# SCH_Protoboard-2x5x17-2_54-FR4_2026-02-2.net
KiCad netlist of a schematic drawn in EasyEDA
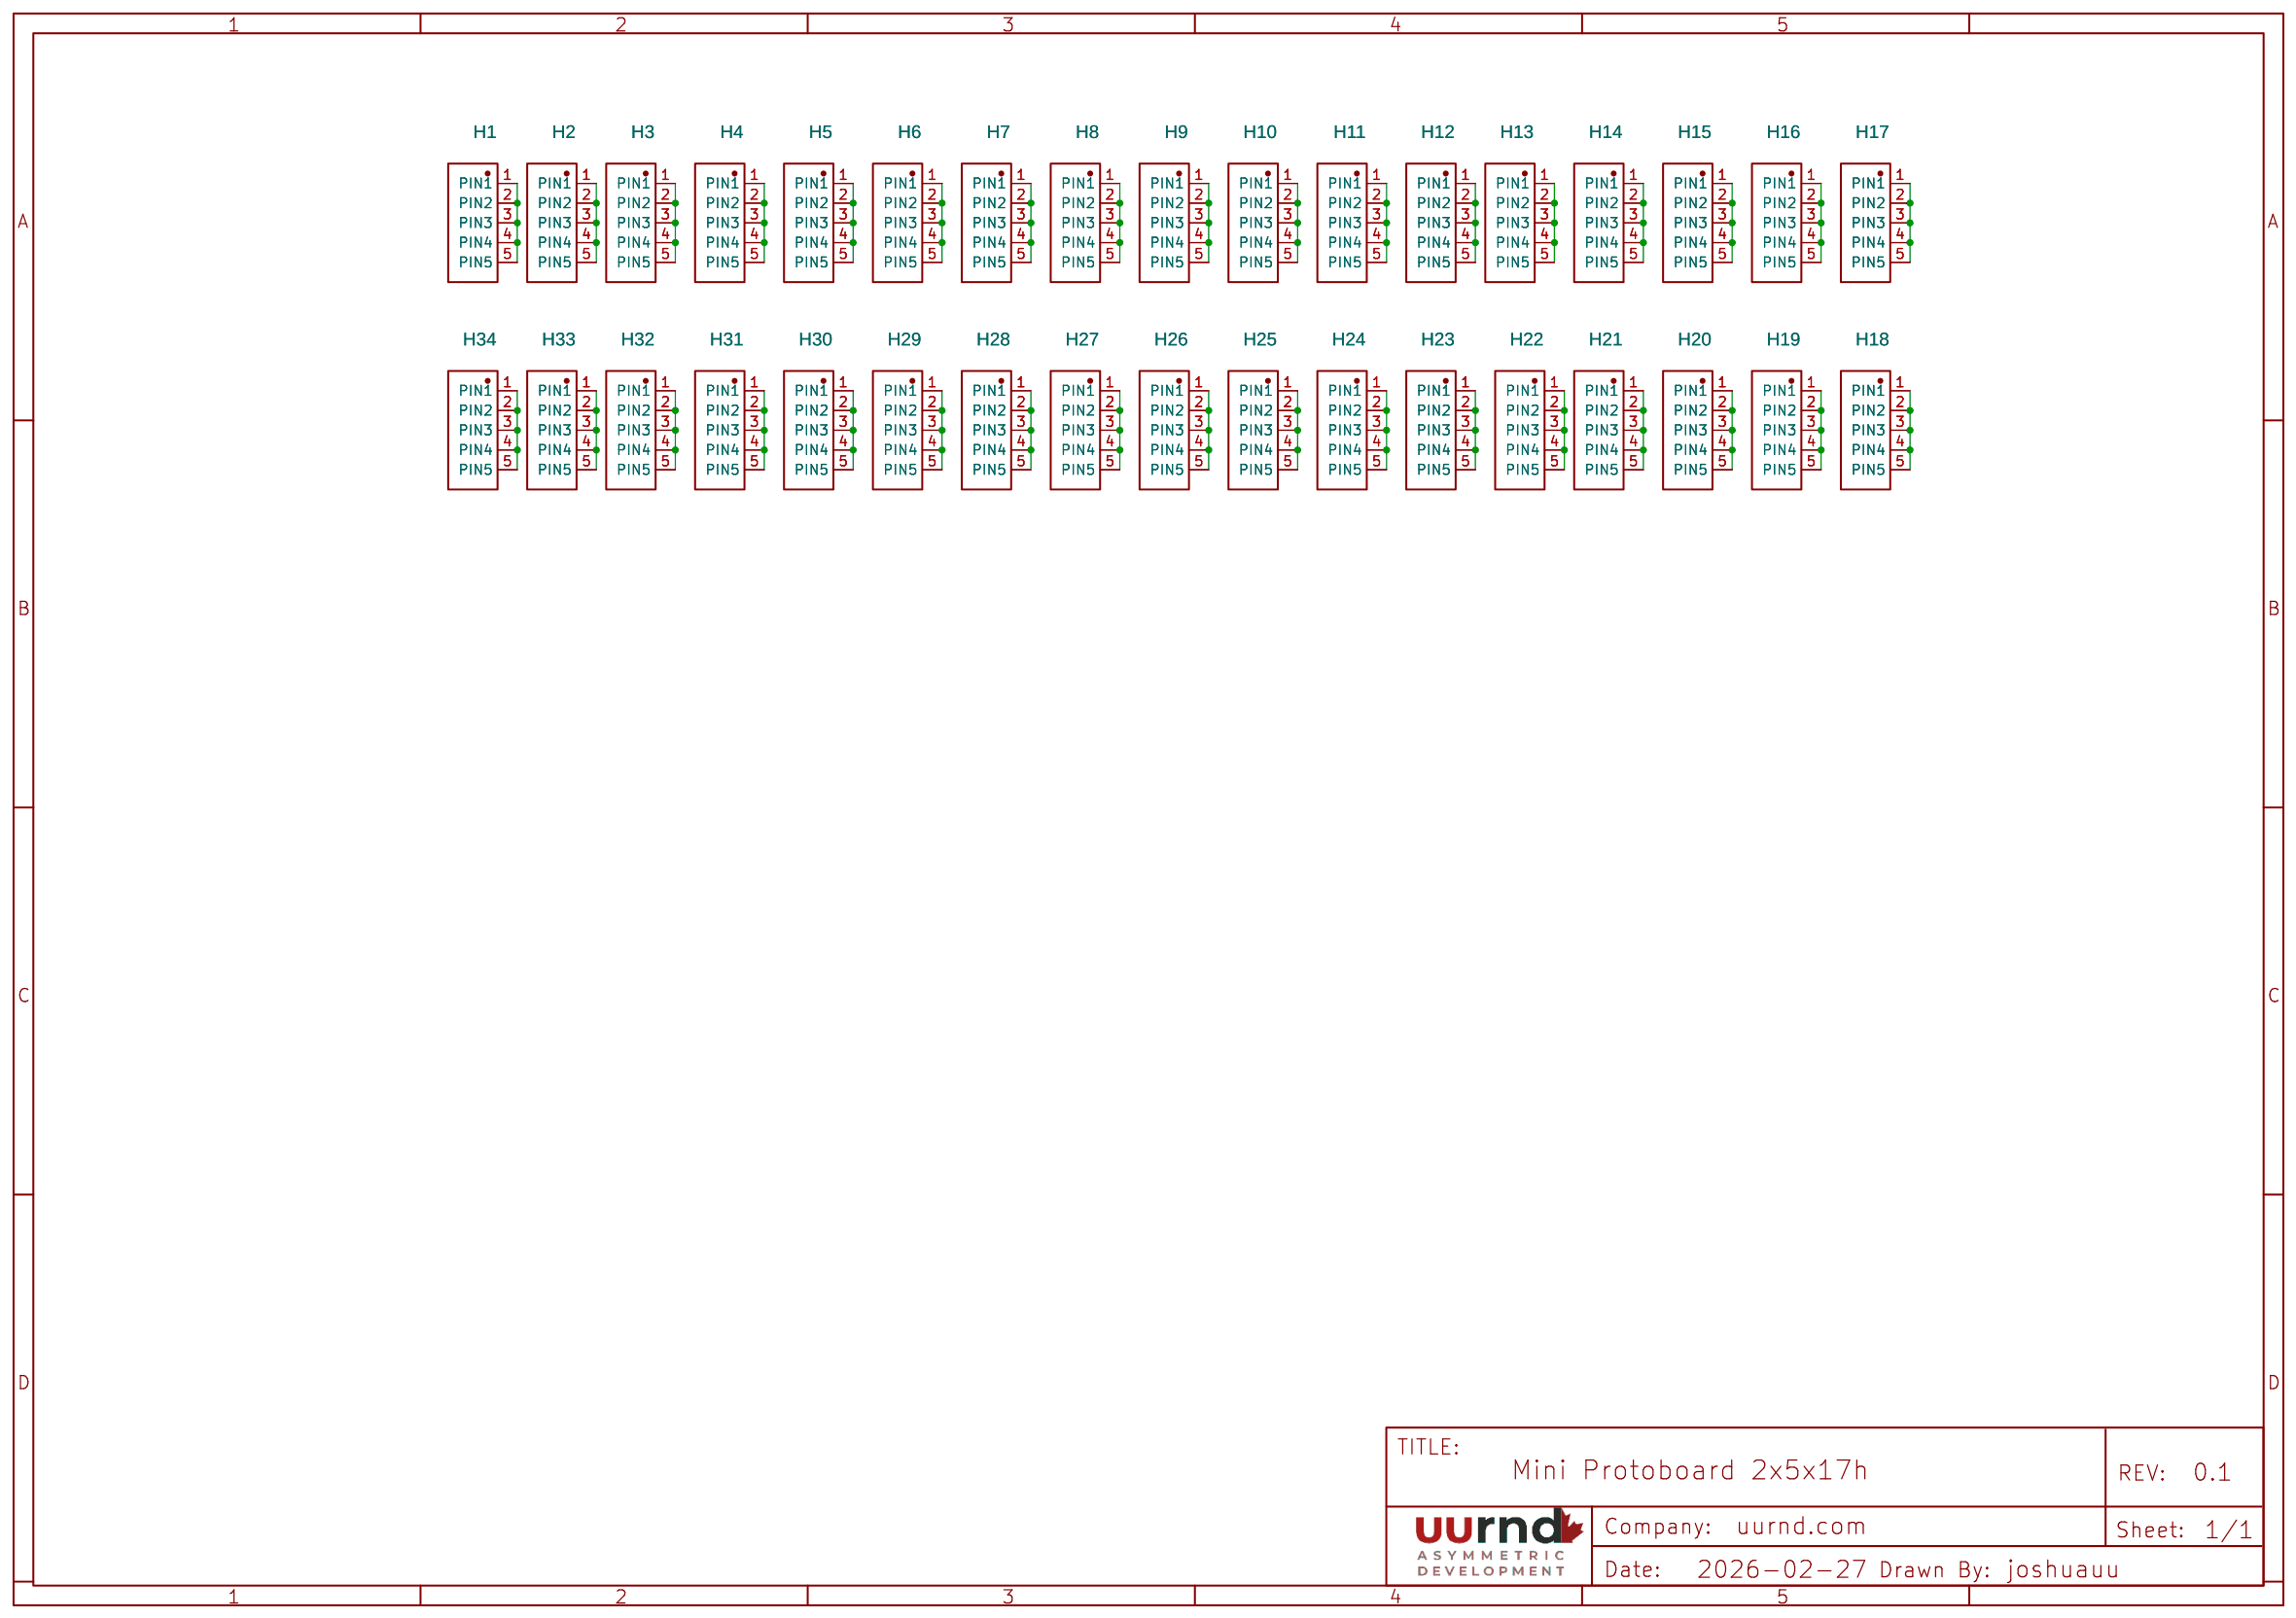
[diagram p0: schematic sheet]

(export (version "E")
  (design (tool "Eeschema 10.0.6"))
  (components
    (comp (ref "H1")
      (value "UU TOP SINGLE SIDE HEADER_2.54MM_1X5P")
      (fields (field (name "Manufacturer") "uuinc"))
      (libsource (lib "") (part "UU TOP SINGLE SIDE HEADER_2.54MM_1X5P"))
    )
    (comp (ref "H2")
      (value "UU TOP SINGLE SIDE HEADER_2.54MM_1X5P")
      (fields (field (name "Manufacturer") "uuinc"))
      (libsource (lib "") (part "UU TOP SINGLE SIDE HEADER_2.54MM_1X5P"))
    )
    (comp (ref "H3")
      (value "UU TOP SINGLE SIDE HEADER_2.54MM_1X5P")
      (fields (field (name "Manufacturer") "uuinc"))
      (libsource (lib "") (part "UU TOP SINGLE SIDE HEADER_2.54MM_1X5P"))
    )
    (comp (ref "H4")
      (value "UU TOP SINGLE SIDE HEADER_2.54MM_1X5P")
      (fields (field (name "Manufacturer") "uuinc"))
      (libsource (lib "") (part "UU TOP SINGLE SIDE HEADER_2.54MM_1X5P"))
    )
    (comp (ref "H5")
      (value "UU TOP SINGLE SIDE HEADER_2.54MM_1X5P")
      (fields (field (name "Manufacturer") "uuinc"))
      (libsource (lib "") (part "UU TOP SINGLE SIDE HEADER_2.54MM_1X5P"))
    )
    (comp (ref "H6")
      (value "UU TOP SINGLE SIDE HEADER_2.54MM_1X5P")
      (fields (field (name "Manufacturer") "uuinc"))
      (libsource (lib "") (part "UU TOP SINGLE SIDE HEADER_2.54MM_1X5P"))
    )
    (comp (ref "H7")
      (value "UU TOP SINGLE SIDE HEADER_2.54MM_1X5P")
      (fields (field (name "Manufacturer") "uuinc"))
      (libsource (lib "") (part "UU TOP SINGLE SIDE HEADER_2.54MM_1X5P"))
    )
    (comp (ref "H8")
      (value "UU TOP SINGLE SIDE HEADER_2.54MM_1X5P")
      (fields (field (name "Manufacturer") "uuinc"))
      (libsource (lib "") (part "UU TOP SINGLE SIDE HEADER_2.54MM_1X5P"))
    )
    (comp (ref "H9")
      (value "UU TOP SINGLE SIDE HEADER_2.54MM_1X5P")
      (fields (field (name "Manufacturer") "uuinc"))
      (libsource (lib "") (part "UU TOP SINGLE SIDE HEADER_2.54MM_1X5P"))
    )
    (comp (ref "H10")
      (value "UU TOP SINGLE SIDE HEADER_2.54MM_1X5P")
      (fields (field (name "Manufacturer") "uuinc"))
      (libsource (lib "") (part "UU TOP SINGLE SIDE HEADER_2.54MM_1X5P"))
    )
    (comp (ref "H11")
      (value "UU TOP SINGLE SIDE HEADER_2.54MM_1X5P")
      (fields (field (name "Manufacturer") "uuinc"))
      (libsource (lib "") (part "UU TOP SINGLE SIDE HEADER_2.54MM_1X5P"))
    )
    (comp (ref "H12")
      (value "UU TOP SINGLE SIDE HEADER_2.54MM_1X5P")
      (fields (field (name "Manufacturer") "uuinc"))
      (libsource (lib "") (part "UU TOP SINGLE SIDE HEADER_2.54MM_1X5P"))
    )
    (comp (ref "H13")
      (value "UU TOP SINGLE SIDE HEADER_2.54MM_1X5P")
      (fields (field (name "Manufacturer") "uuinc"))
      (libsource (lib "") (part "UU TOP SINGLE SIDE HEADER_2.54MM_1X5P"))
    )
    (comp (ref "H14")
      (value "UU TOP SINGLE SIDE HEADER_2.54MM_1X5P")
      (fields (field (name "Manufacturer") "uuinc"))
      (libsource (lib "") (part "UU TOP SINGLE SIDE HEADER_2.54MM_1X5P"))
    )
    (comp (ref "H15")
      (value "UU TOP SINGLE SIDE HEADER_2.54MM_1X5P")
      (fields (field (name "Manufacturer") "uuinc"))
      (libsource (lib "") (part "UU TOP SINGLE SIDE HEADER_2.54MM_1X5P"))
    )
    (comp (ref "H16")
      (value "UU TOP SINGLE SIDE HEADER_2.54MM_1X5P")
      (fields (field (name "Manufacturer") "uuinc"))
      (libsource (lib "") (part "UU TOP SINGLE SIDE HEADER_2.54MM_1X5P"))
    )
    (comp (ref "H17")
      (value "UU TOP SINGLE SIDE HEADER_2.54MM_1X5P")
      (fields (field (name "Manufacturer") "uuinc"))
      (libsource (lib "") (part "UU TOP SINGLE SIDE HEADER_2.54MM_1X5P"))
    )
    (comp (ref "H18")
      (value "UU TOP SINGLE SIDE HEADER_2.54MM_1X5P")
      (fields (field (name "Manufacturer") "uuinc"))
      (libsource (lib "") (part "UU TOP SINGLE SIDE HEADER_2.54MM_1X5P"))
    )
    (comp (ref "H19")
      (value "UU TOP SINGLE SIDE HEADER_2.54MM_1X5P")
      (fields (field (name "Manufacturer") "uuinc"))
      (libsource (lib "") (part "UU TOP SINGLE SIDE HEADER_2.54MM_1X5P"))
    )
    (comp (ref "H20")
      (value "UU TOP SINGLE SIDE HEADER_2.54MM_1X5P")
      (fields (field (name "Manufacturer") "uuinc"))
      (libsource (lib "") (part "UU TOP SINGLE SIDE HEADER_2.54MM_1X5P"))
    )
    (comp (ref "H21")
      (value "UU TOP SINGLE SIDE HEADER_2.54MM_1X5P")
      (fields (field (name "Manufacturer") "uuinc"))
      (libsource (lib "") (part "UU TOP SINGLE SIDE HEADER_2.54MM_1X5P"))
    )
    (comp (ref "H22")
      (value "UU TOP SINGLE SIDE HEADER_2.54MM_1X5P")
      (fields (field (name "Manufacturer") "uuinc"))
      (libsource (lib "") (part "UU TOP SINGLE SIDE HEADER_2.54MM_1X5P"))
    )
    (comp (ref "H23")
      (value "UU TOP SINGLE SIDE HEADER_2.54MM_1X5P")
      (fields (field (name "Manufacturer") "uuinc"))
      (libsource (lib "") (part "UU TOP SINGLE SIDE HEADER_2.54MM_1X5P"))
    )
    (comp (ref "H24")
      (value "UU TOP SINGLE SIDE HEADER_2.54MM_1X5P")
      (fields (field (name "Manufacturer") "uuinc"))
      (libsource (lib "") (part "UU TOP SINGLE SIDE HEADER_2.54MM_1X5P"))
    )
    (comp (ref "H25")
      (value "UU TOP SINGLE SIDE HEADER_2.54MM_1X5P")
      (fields (field (name "Manufacturer") "uuinc"))
      (libsource (lib "") (part "UU TOP SINGLE SIDE HEADER_2.54MM_1X5P"))
    )
    (comp (ref "H26")
      (value "UU TOP SINGLE SIDE HEADER_2.54MM_1X5P")
      (fields (field (name "Manufacturer") "uuinc"))
      (libsource (lib "") (part "UU TOP SINGLE SIDE HEADER_2.54MM_1X5P"))
    )
    (comp (ref "H27")
      (value "UU TOP SINGLE SIDE HEADER_2.54MM_1X5P")
      (fields (field (name "Manufacturer") "uuinc"))
      (libsource (lib "") (part "UU TOP SINGLE SIDE HEADER_2.54MM_1X5P"))
    )
    (comp (ref "H28")
      (value "UU TOP SINGLE SIDE HEADER_2.54MM_1X5P")
      (fields (field (name "Manufacturer") "uuinc"))
      (libsource (lib "") (part "UU TOP SINGLE SIDE HEADER_2.54MM_1X5P"))
    )
    (comp (ref "H29")
      (value "UU TOP SINGLE SIDE HEADER_2.54MM_1X5P")
      (fields (field (name "Manufacturer") "uuinc"))
      (libsource (lib "") (part "UU TOP SINGLE SIDE HEADER_2.54MM_1X5P"))
    )
    (comp (ref "H30")
      (value "UU TOP SINGLE SIDE HEADER_2.54MM_1X5P")
      (fields (field (name "Manufacturer") "uuinc"))
      (libsource (lib "") (part "UU TOP SINGLE SIDE HEADER_2.54MM_1X5P"))
    )
    (comp (ref "H31")
      (value "UU TOP SINGLE SIDE HEADER_2.54MM_1X5P")
      (fields (field (name "Manufacturer") "uuinc"))
      (libsource (lib "") (part "UU TOP SINGLE SIDE HEADER_2.54MM_1X5P"))
    )
    (comp (ref "H32")
      (value "UU TOP SINGLE SIDE HEADER_2.54MM_1X5P")
      (fields (field (name "Manufacturer") "uuinc"))
      (libsource (lib "") (part "UU TOP SINGLE SIDE HEADER_2.54MM_1X5P"))
    )
    (comp (ref "H33")
      (value "UU TOP SINGLE SIDE HEADER_2.54MM_1X5P")
      (fields (field (name "Manufacturer") "uuinc"))
      (libsource (lib "") (part "UU TOP SINGLE SIDE HEADER_2.54MM_1X5P"))
    )
    (comp (ref "H34")
      (value "UU TOP SINGLE SIDE HEADER_2.54MM_1X5P")
      (fields (field (name "Manufacturer") "uuinc"))
      (libsource (lib "") (part "UU TOP SINGLE SIDE HEADER_2.54MM_1X5P"))
    )
  )
  (nets
    (net (code "1") (name "Net-(H1-PIN1)") (class "Default")
      (node (ref "H1") (pin "1") (pinfunction "PIN1_1") (pintype "unspecified"))
      (node (ref "H1") (pin "2") (pinfunction "PIN2_2") (pintype "unspecified"))
      (node (ref "H1") (pin "3") (pinfunction "PIN3_3") (pintype "unspecified"))
      (node (ref "H1") (pin "4") (pinfunction "PIN4_4") (pintype "unspecified"))
      (node (ref "H1") (pin "5") (pinfunction "PIN5_5") (pintype "unspecified"))
    )
    (net (code "2") (name "Net-(H2-PIN1)") (class "Default")
      (node (ref "H2") (pin "1") (pinfunction "PIN1_1") (pintype "unspecified"))
      (node (ref "H2") (pin "2") (pinfunction "PIN2_2") (pintype "unspecified"))
      (node (ref "H2") (pin "3") (pinfunction "PIN3_3") (pintype "unspecified"))
      (node (ref "H2") (pin "4") (pinfunction "PIN4_4") (pintype "unspecified"))
      (node (ref "H2") (pin "5") (pinfunction "PIN5_5") (pintype "unspecified"))
    )
    (net (code "3") (name "Net-(H3-PIN1)") (class "Default")
      (node (ref "H3") (pin "1") (pinfunction "PIN1_1") (pintype "unspecified"))
      (node (ref "H3") (pin "2") (pinfunction "PIN2_2") (pintype "unspecified"))
      (node (ref "H3") (pin "3") (pinfunction "PIN3_3") (pintype "unspecified"))
      (node (ref "H3") (pin "4") (pinfunction "PIN4_4") (pintype "unspecified"))
      (node (ref "H3") (pin "5") (pinfunction "PIN5_5") (pintype "unspecified"))
    )
    (net (code "4") (name "Net-(H4-PIN1)") (class "Default")
      (node (ref "H4") (pin "1") (pinfunction "PIN1_1") (pintype "unspecified"))
      (node (ref "H4") (pin "2") (pinfunction "PIN2_2") (pintype "unspecified"))
      (node (ref "H4") (pin "3") (pinfunction "PIN3_3") (pintype "unspecified"))
      (node (ref "H4") (pin "4") (pinfunction "PIN4_4") (pintype "unspecified"))
      (node (ref "H4") (pin "5") (pinfunction "PIN5_5") (pintype "unspecified"))
    )
    (net (code "5") (name "Net-(H5-PIN1)") (class "Default")
      (node (ref "H5") (pin "1") (pinfunction "PIN1_1") (pintype "unspecified"))
      (node (ref "H5") (pin "2") (pinfunction "PIN2_2") (pintype "unspecified"))
      (node (ref "H5") (pin "3") (pinfunction "PIN3_3") (pintype "unspecified"))
      (node (ref "H5") (pin "4") (pinfunction "PIN4_4") (pintype "unspecified"))
      (node (ref "H5") (pin "5") (pinfunction "PIN5_5") (pintype "unspecified"))
    )
    (net (code "6") (name "Net-(H6-PIN1)") (class "Default")
      (node (ref "H6") (pin "1") (pinfunction "PIN1_1") (pintype "unspecified"))
      (node (ref "H6") (pin "2") (pinfunction "PIN2_2") (pintype "unspecified"))
      (node (ref "H6") (pin "3") (pinfunction "PIN3_3") (pintype "unspecified"))
      (node (ref "H6") (pin "4") (pinfunction "PIN4_4") (pintype "unspecified"))
      (node (ref "H6") (pin "5") (pinfunction "PIN5_5") (pintype "unspecified"))
    )
    (net (code "7") (name "Net-(H7-PIN1)") (class "Default")
      (node (ref "H7") (pin "1") (pinfunction "PIN1_1") (pintype "unspecified"))
      (node (ref "H7") (pin "2") (pinfunction "PIN2_2") (pintype "unspecified"))
      (node (ref "H7") (pin "3") (pinfunction "PIN3_3") (pintype "unspecified"))
      (node (ref "H7") (pin "4") (pinfunction "PIN4_4") (pintype "unspecified"))
      (node (ref "H7") (pin "5") (pinfunction "PIN5_5") (pintype "unspecified"))
    )
    (net (code "8") (name "Net-(H8-PIN1)") (class "Default")
      (node (ref "H8") (pin "1") (pinfunction "PIN1_1") (pintype "unspecified"))
      (node (ref "H8") (pin "2") (pinfunction "PIN2_2") (pintype "unspecified"))
      (node (ref "H8") (pin "3") (pinfunction "PIN3_3") (pintype "unspecified"))
      (node (ref "H8") (pin "4") (pinfunction "PIN4_4") (pintype "unspecified"))
      (node (ref "H8") (pin "5") (pinfunction "PIN5_5") (pintype "unspecified"))
    )
    (net (code "9") (name "Net-(H9-PIN1)") (class "Default")
      (node (ref "H9") (pin "1") (pinfunction "PIN1_1") (pintype "unspecified"))
      (node (ref "H9") (pin "2") (pinfunction "PIN2_2") (pintype "unspecified"))
      (node (ref "H9") (pin "3") (pinfunction "PIN3_3") (pintype "unspecified"))
      (node (ref "H9") (pin "4") (pinfunction "PIN4_4") (pintype "unspecified"))
      (node (ref "H9") (pin "5") (pinfunction "PIN5_5") (pintype "unspecified"))
    )
    (net (code "10") (name "Net-(H10-PIN1)") (class "Default")
      (node (ref "H10") (pin "1") (pinfunction "PIN1_1") (pintype "unspecified"))
      (node (ref "H10") (pin "2") (pinfunction "PIN2_2") (pintype "unspecified"))
      (node (ref "H10") (pin "3") (pinfunction "PIN3_3") (pintype "unspecified"))
      (node (ref "H10") (pin "4") (pinfunction "PIN4_4") (pintype "unspecified"))
      (node (ref "H10") (pin "5") (pinfunction "PIN5_5") (pintype "unspecified"))
    )
    (net (code "11") (name "Net-(H11-PIN1)") (class "Default")
      (node (ref "H11") (pin "1") (pinfunction "PIN1_1") (pintype "unspecified"))
      (node (ref "H11") (pin "2") (pinfunction "PIN2_2") (pintype "unspecified"))
      (node (ref "H11") (pin "3") (pinfunction "PIN3_3") (pintype "unspecified"))
      (node (ref "H11") (pin "4") (pinfunction "PIN4_4") (pintype "unspecified"))
      (node (ref "H11") (pin "5") (pinfunction "PIN5_5") (pintype "unspecified"))
    )
    (net (code "12") (name "Net-(H12-PIN1)") (class "Default")
      (node (ref "H12") (pin "1") (pinfunction "PIN1_1") (pintype "unspecified"))
      (node (ref "H12") (pin "2") (pinfunction "PIN2_2") (pintype "unspecified"))
      (node (ref "H12") (pin "3") (pinfunction "PIN3_3") (pintype "unspecified"))
      (node (ref "H12") (pin "4") (pinfunction "PIN4_4") (pintype "unspecified"))
      (node (ref "H12") (pin "5") (pinfunction "PIN5_5") (pintype "unspecified"))
    )
    (net (code "13") (name "Net-(H13-PIN1)") (class "Default")
      (node (ref "H13") (pin "1") (pinfunction "PIN1_1") (pintype "unspecified"))
      (node (ref "H13") (pin "2") (pinfunction "PIN2_2") (pintype "unspecified"))
      (node (ref "H13") (pin "3") (pinfunction "PIN3_3") (pintype "unspecified"))
      (node (ref "H13") (pin "4") (pinfunction "PIN4_4") (pintype "unspecified"))
      (node (ref "H13") (pin "5") (pinfunction "PIN5_5") (pintype "unspecified"))
    )
    (net (code "14") (name "Net-(H14-PIN1)") (class "Default")
      (node (ref "H14") (pin "1") (pinfunction "PIN1_1") (pintype "unspecified"))
      (node (ref "H14") (pin "2") (pinfunction "PIN2_2") (pintype "unspecified"))
      (node (ref "H14") (pin "3") (pinfunction "PIN3_3") (pintype "unspecified"))
      (node (ref "H14") (pin "4") (pinfunction "PIN4_4") (pintype "unspecified"))
      (node (ref "H14") (pin "5") (pinfunction "PIN5_5") (pintype "unspecified"))
    )
    (net (code "15") (name "Net-(H15-PIN1)") (class "Default")
      (node (ref "H15") (pin "1") (pinfunction "PIN1_1") (pintype "unspecified"))
      (node (ref "H15") (pin "2") (pinfunction "PIN2_2") (pintype "unspecified"))
      (node (ref "H15") (pin "3") (pinfunction "PIN3_3") (pintype "unspecified"))
      (node (ref "H15") (pin "4") (pinfunction "PIN4_4") (pintype "unspecified"))
      (node (ref "H15") (pin "5") (pinfunction "PIN5_5") (pintype "unspecified"))
    )
    (net (code "16") (name "Net-(H16-PIN1)") (class "Default")
      (node (ref "H16") (pin "1") (pinfunction "PIN1_1") (pintype "unspecified"))
      (node (ref "H16") (pin "2") (pinfunction "PIN2_2") (pintype "unspecified"))
      (node (ref "H16") (pin "3") (pinfunction "PIN3_3") (pintype "unspecified"))
      (node (ref "H16") (pin "4") (pinfunction "PIN4_4") (pintype "unspecified"))
      (node (ref "H16") (pin "5") (pinfunction "PIN5_5") (pintype "unspecified"))
    )
    (net (code "17") (name "Net-(H17-PIN1)") (class "Default")
      (node (ref "H17") (pin "1") (pinfunction "PIN1_1") (pintype "unspecified"))
      (node (ref "H17") (pin "2") (pinfunction "PIN2_2") (pintype "unspecified"))
      (node (ref "H17") (pin "3") (pinfunction "PIN3_3") (pintype "unspecified"))
      (node (ref "H17") (pin "4") (pinfunction "PIN4_4") (pintype "unspecified"))
      (node (ref "H17") (pin "5") (pinfunction "PIN5_5") (pintype "unspecified"))
    )
    (net (code "18") (name "Net-(H18-PIN1)") (class "Default")
      (node (ref "H18") (pin "1") (pinfunction "PIN1_1") (pintype "unspecified"))
      (node (ref "H18") (pin "2") (pinfunction "PIN2_2") (pintype "unspecified"))
      (node (ref "H18") (pin "3") (pinfunction "PIN3_3") (pintype "unspecified"))
      (node (ref "H18") (pin "4") (pinfunction "PIN4_4") (pintype "unspecified"))
      (node (ref "H18") (pin "5") (pinfunction "PIN5_5") (pintype "unspecified"))
    )
    (net (code "19") (name "Net-(H19-PIN1)") (class "Default")
      (node (ref "H19") (pin "1") (pinfunction "PIN1_1") (pintype "unspecified"))
      (node (ref "H19") (pin "2") (pinfunction "PIN2_2") (pintype "unspecified"))
      (node (ref "H19") (pin "3") (pinfunction "PIN3_3") (pintype "unspecified"))
      (node (ref "H19") (pin "4") (pinfunction "PIN4_4") (pintype "unspecified"))
      (node (ref "H19") (pin "5") (pinfunction "PIN5_5") (pintype "unspecified"))
    )
    (net (code "20") (name "Net-(H20-PIN1)") (class "Default")
      (node (ref "H20") (pin "1") (pinfunction "PIN1_1") (pintype "unspecified"))
      (node (ref "H20") (pin "2") (pinfunction "PIN2_2") (pintype "unspecified"))
      (node (ref "H20") (pin "3") (pinfunction "PIN3_3") (pintype "unspecified"))
      (node (ref "H20") (pin "4") (pinfunction "PIN4_4") (pintype "unspecified"))
      (node (ref "H20") (pin "5") (pinfunction "PIN5_5") (pintype "unspecified"))
    )
    (net (code "21") (name "Net-(H21-PIN1)") (class "Default")
      (node (ref "H21") (pin "1") (pinfunction "PIN1_1") (pintype "unspecified"))
      (node (ref "H21") (pin "2") (pinfunction "PIN2_2") (pintype "unspecified"))
      (node (ref "H21") (pin "3") (pinfunction "PIN3_3") (pintype "unspecified"))
      (node (ref "H21") (pin "4") (pinfunction "PIN4_4") (pintype "unspecified"))
      (node (ref "H21") (pin "5") (pinfunction "PIN5_5") (pintype "unspecified"))
    )
    (net (code "22") (name "Net-(H22-PIN1)") (class "Default")
      (node (ref "H22") (pin "1") (pinfunction "PIN1_1") (pintype "unspecified"))
      (node (ref "H22") (pin "2") (pinfunction "PIN2_2") (pintype "unspecified"))
      (node (ref "H22") (pin "3") (pinfunction "PIN3_3") (pintype "unspecified"))
      (node (ref "H22") (pin "4") (pinfunction "PIN4_4") (pintype "unspecified"))
      (node (ref "H22") (pin "5") (pinfunction "PIN5_5") (pintype "unspecified"))
    )
    (net (code "23") (name "Net-(H23-PIN1)") (class "Default")
      (node (ref "H23") (pin "1") (pinfunction "PIN1_1") (pintype "unspecified"))
      (node (ref "H23") (pin "2") (pinfunction "PIN2_2") (pintype "unspecified"))
      (node (ref "H23") (pin "3") (pinfunction "PIN3_3") (pintype "unspecified"))
      (node (ref "H23") (pin "4") (pinfunction "PIN4_4") (pintype "unspecified"))
      (node (ref "H23") (pin "5") (pinfunction "PIN5_5") (pintype "unspecified"))
    )
    (net (code "24") (name "Net-(H24-PIN1)") (class "Default")
      (node (ref "H24") (pin "1") (pinfunction "PIN1_1") (pintype "unspecified"))
      (node (ref "H24") (pin "2") (pinfunction "PIN2_2") (pintype "unspecified"))
      (node (ref "H24") (pin "3") (pinfunction "PIN3_3") (pintype "unspecified"))
      (node (ref "H24") (pin "4") (pinfunction "PIN4_4") (pintype "unspecified"))
      (node (ref "H24") (pin "5") (pinfunction "PIN5_5") (pintype "unspecified"))
    )
    (net (code "25") (name "Net-(H25-PIN1)") (class "Default")
      (node (ref "H25") (pin "1") (pinfunction "PIN1_1") (pintype "unspecified"))
      (node (ref "H25") (pin "2") (pinfunction "PIN2_2") (pintype "unspecified"))
      (node (ref "H25") (pin "3") (pinfunction "PIN3_3") (pintype "unspecified"))
      (node (ref "H25") (pin "4") (pinfunction "PIN4_4") (pintype "unspecified"))
      (node (ref "H25") (pin "5") (pinfunction "PIN5_5") (pintype "unspecified"))
    )
    (net (code "26") (name "Net-(H26-PIN1)") (class "Default")
      (node (ref "H26") (pin "1") (pinfunction "PIN1_1") (pintype "unspecified"))
      (node (ref "H26") (pin "2") (pinfunction "PIN2_2") (pintype "unspecified"))
      (node (ref "H26") (pin "3") (pinfunction "PIN3_3") (pintype "unspecified"))
      (node (ref "H26") (pin "4") (pinfunction "PIN4_4") (pintype "unspecified"))
      (node (ref "H26") (pin "5") (pinfunction "PIN5_5") (pintype "unspecified"))
    )
    (net (code "27") (name "Net-(H27-PIN1)") (class "Default")
      (node (ref "H27") (pin "1") (pinfunction "PIN1_1") (pintype "unspecified"))
      (node (ref "H27") (pin "2") (pinfunction "PIN2_2") (pintype "unspecified"))
      (node (ref "H27") (pin "3") (pinfunction "PIN3_3") (pintype "unspecified"))
      (node (ref "H27") (pin "4") (pinfunction "PIN4_4") (pintype "unspecified"))
      (node (ref "H27") (pin "5") (pinfunction "PIN5_5") (pintype "unspecified"))
    )
    (net (code "28") (name "Net-(H28-PIN1)") (class "Default")
      (node (ref "H28") (pin "1") (pinfunction "PIN1_1") (pintype "unspecified"))
      (node (ref "H28") (pin "2") (pinfunction "PIN2_2") (pintype "unspecified"))
      (node (ref "H28") (pin "3") (pinfunction "PIN3_3") (pintype "unspecified"))
      (node (ref "H28") (pin "4") (pinfunction "PIN4_4") (pintype "unspecified"))
      (node (ref "H28") (pin "5") (pinfunction "PIN5_5") (pintype "unspecified"))
    )
    (net (code "29") (name "Net-(H29-PIN1)") (class "Default")
      (node (ref "H29") (pin "1") (pinfunction "PIN1_1") (pintype "unspecified"))
      (node (ref "H29") (pin "2") (pinfunction "PIN2_2") (pintype "unspecified"))
      (node (ref "H29") (pin "3") (pinfunction "PIN3_3") (pintype "unspecified"))
      (node (ref "H29") (pin "4") (pinfunction "PIN4_4") (pintype "unspecified"))
      (node (ref "H29") (pin "5") (pinfunction "PIN5_5") (pintype "unspecified"))
    )
    (net (code "30") (name "Net-(H30-PIN1)") (class "Default")
      (node (ref "H30") (pin "1") (pinfunction "PIN1_1") (pintype "unspecified"))
      (node (ref "H30") (pin "2") (pinfunction "PIN2_2") (pintype "unspecified"))
      (node (ref "H30") (pin "3") (pinfunction "PIN3_3") (pintype "unspecified"))
      (node (ref "H30") (pin "4") (pinfunction "PIN4_4") (pintype "unspecified"))
      (node (ref "H30") (pin "5") (pinfunction "PIN5_5") (pintype "unspecified"))
    )
    (net (code "31") (name "Net-(H31-PIN1)") (class "Default")
      (node (ref "H31") (pin "1") (pinfunction "PIN1_1") (pintype "unspecified"))
      (node (ref "H31") (pin "2") (pinfunction "PIN2_2") (pintype "unspecified"))
      (node (ref "H31") (pin "3") (pinfunction "PIN3_3") (pintype "unspecified"))
      (node (ref "H31") (pin "4") (pinfunction "PIN4_4") (pintype "unspecified"))
      (node (ref "H31") (pin "5") (pinfunction "PIN5_5") (pintype "unspecified"))
    )
    (net (code "32") (name "Net-(H32-PIN1)") (class "Default")
      (node (ref "H32") (pin "1") (pinfunction "PIN1_1") (pintype "unspecified"))
      (node (ref "H32") (pin "2") (pinfunction "PIN2_2") (pintype "unspecified"))
      (node (ref "H32") (pin "3") (pinfunction "PIN3_3") (pintype "unspecified"))
      (node (ref "H32") (pin "4") (pinfunction "PIN4_4") (pintype "unspecified"))
      (node (ref "H32") (pin "5") (pinfunction "PIN5_5") (pintype "unspecified"))
    )
    (net (code "33") (name "Net-(H33-PIN1)") (class "Default")
      (node (ref "H33") (pin "1") (pinfunction "PIN1_1") (pintype "unspecified"))
      (node (ref "H33") (pin "2") (pinfunction "PIN2_2") (pintype "unspecified"))
      (node (ref "H33") (pin "3") (pinfunction "PIN3_3") (pintype "unspecified"))
      (node (ref "H33") (pin "4") (pinfunction "PIN4_4") (pintype "unspecified"))
      (node (ref "H33") (pin "5") (pinfunction "PIN5_5") (pintype "unspecified"))
    )
    (net (code "34") (name "Net-(H34-PIN1)") (class "Default")
      (node (ref "H34") (pin "1") (pinfunction "PIN1_1") (pintype "unspecified"))
      (node (ref "H34") (pin "2") (pinfunction "PIN2_2") (pintype "unspecified"))
      (node (ref "H34") (pin "3") (pinfunction "PIN3_3") (pintype "unspecified"))
      (node (ref "H34") (pin "4") (pinfunction "PIN4_4") (pintype "unspecified"))
      (node (ref "H34") (pin "5") (pinfunction "PIN5_5") (pintype "unspecified"))
    )
  )
)
